# PowerDistributorX30V2.net
KiCad netlist of a schematic drawn in EAGLE
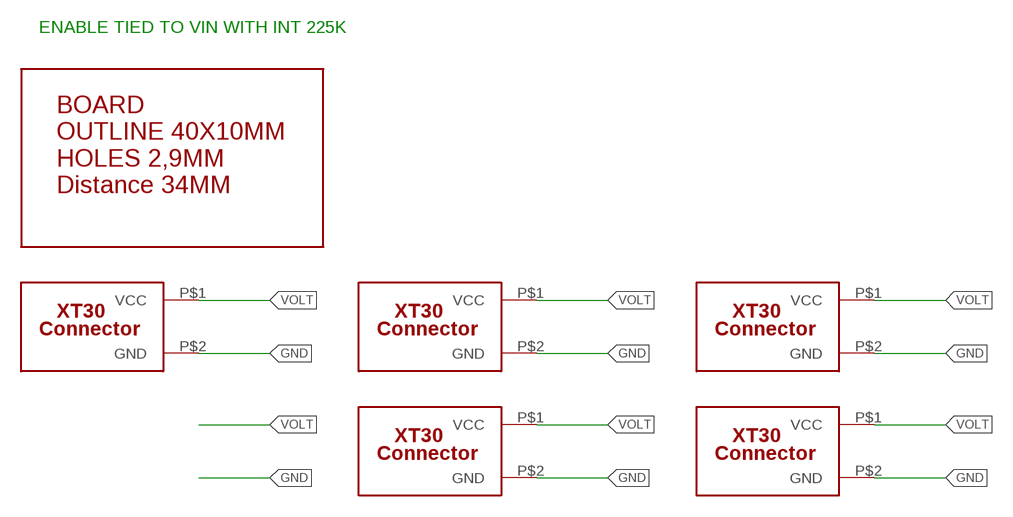
[diagram p0: schematic, sheet 1]

(export (version "E")
  (design (tool "Eeschema 10.0.6"))
  (components
    (comp (ref "U$1")
      (value "BOARD40X10")
      (footprint "eagle-import:BOARD_40X10-34HOLES")
      (libsource (lib "eagle-import") (part "BOARD40X10"))
    )
    (comp (ref "U$2")
      (value "XT30")
      (footprint "eagle-import:XT30-VERT")
      (libsource (lib "eagle-import") (part "XT30"))
    )
    (comp (ref "U$4")
      (value "XT30")
      (footprint "eagle-import:XT30-VERT")
      (libsource (lib "eagle-import") (part "XT30"))
    )
    (comp (ref "U$5")
      (value "XT30")
      (footprint "eagle-import:XT30-VERT")
      (libsource (lib "eagle-import") (part "XT30"))
    )
    (comp (ref "U$6")
      (value "XT30")
      (footprint "eagle-import:XT30-VERT")
      (libsource (lib "eagle-import") (part "XT30"))
    )
    (comp (ref "U$7")
      (value "XT30")
      (footprint "eagle-import:XT30-VERT")
      (libsource (lib "eagle-import") (part "XT30"))
    )
  )
  (nets
    (net (code "1") (name "GND") (class "Default")
      (node (ref "U$2") (pin "P$2") (pinfunction "GND_P$2") (pintype "bidirectional"))
      (node (ref "U$4") (pin "P$2") (pinfunction "GND_P$2") (pintype "bidirectional"))
      (node (ref "U$5") (pin "P$2") (pinfunction "GND_P$2") (pintype "bidirectional"))
      (node (ref "U$6") (pin "P$2") (pinfunction "GND_P$2") (pintype "bidirectional"))
      (node (ref "U$7") (pin "P$2") (pinfunction "GND_P$2") (pintype "bidirectional"))
    )
    (net (code "2") (name "VOLT") (class "Default")
      (node (ref "U$2") (pin "P$1") (pinfunction "VCC_P$1") (pintype "bidirectional"))
      (node (ref "U$4") (pin "P$1") (pinfunction "VCC_P$1") (pintype "bidirectional"))
      (node (ref "U$5") (pin "P$1") (pinfunction "VCC_P$1") (pintype "bidirectional"))
      (node (ref "U$6") (pin "P$1") (pinfunction "VCC_P$1") (pintype "bidirectional"))
      (node (ref "U$7") (pin "P$1") (pinfunction "VCC_P$1") (pintype "bidirectional"))
    )
  )
)
